# Sheet5.net
KiCad netlist of a schematic drawn in Altium Designer
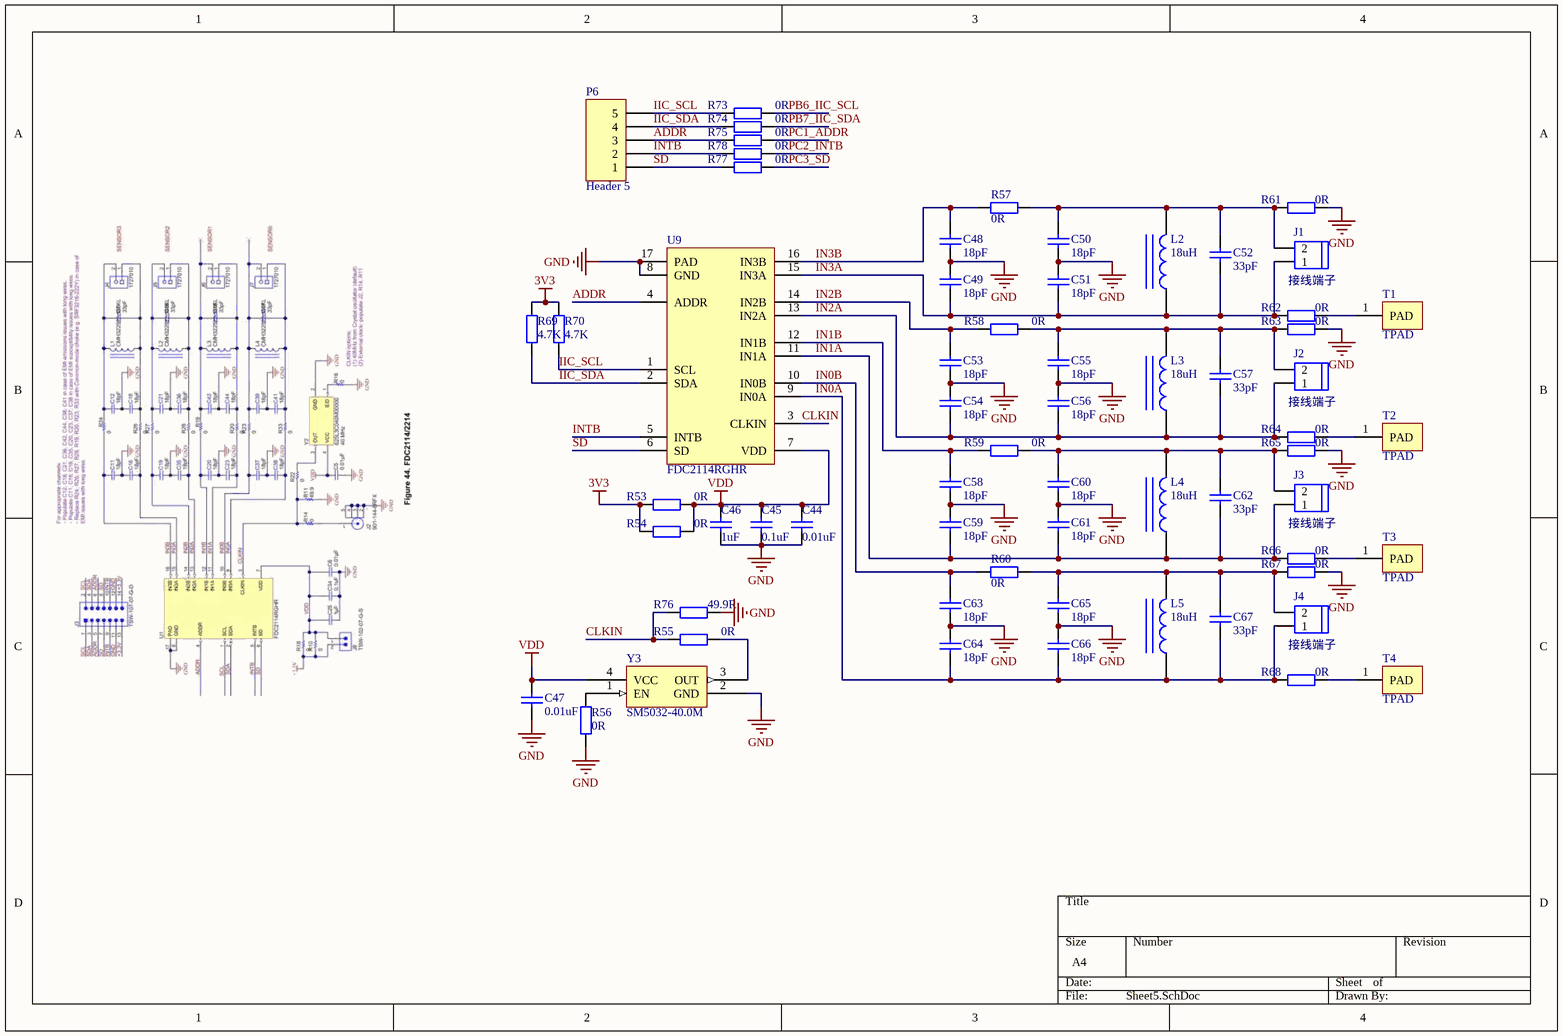
[diagram p0: Sheet5.SchDoc]

(export (version "E")
  (design (tool "Eeschema 10.0.6"))
  (components
    (comp (ref "C44")
      (value "0.01uF")
      (footprint "LC-0603_C")
      (description "贴片电容")
      (libsource (lib "Miscellaneous Devices LC") (part "0603 1uF (105) 10% 50V"))
    )
    (comp (ref "C45")
      (value "0.1uF")
      (footprint "LC-0603_C")
      (description "贴片电容")
      (libsource (lib "Miscellaneous Devices LC") (part "0603 1uF (105) 10% 50V"))
    )
    (comp (ref "C46")
      (value "1uF")
      (footprint "LC-0603_C")
      (description "贴片电容")
      (libsource (lib "Miscellaneous Devices LC") (part "0603 1uF (105) 10% 50V"))
    )
    (comp (ref "C47")
      (value "0.01uF")
      (footprint "LC-0603_C")
      (description "贴片电容")
      (libsource (lib "Miscellaneous Devices LC") (part "0603 1uF (105) 10% 50V"))
    )
    (comp (ref "C48")
      (value "18pF")
      (footprint "LC-0603_C")
      (description "贴片电容")
      (libsource (lib "Miscellaneous Devices LC") (part "0603 1uF (105) 10% 50V"))
    )
    (comp (ref "C49")
      (value "18pF")
      (footprint "LC-0603_C")
      (description "贴片电容")
      (libsource (lib "Miscellaneous Devices LC") (part "0603 1uF (105) 10% 50V"))
    )
    (comp (ref "C50")
      (value "18pF")
      (footprint "LC-0603_C")
      (description "贴片电容")
      (libsource (lib "Miscellaneous Devices LC") (part "0603 1uF (105) 10% 50V"))
    )
    (comp (ref "C51")
      (value "18pF")
      (footprint "LC-0603_C")
      (description "贴片电容")
      (libsource (lib "Miscellaneous Devices LC") (part "0603 1uF (105) 10% 50V"))
    )
    (comp (ref "C52")
      (value "33pF")
      (footprint "LC-0603_C")
      (description "贴片电容")
      (libsource (lib "Miscellaneous Devices LC") (part "0603 1uF (105) 10% 50V"))
    )
    (comp (ref "C53")
      (value "18pF")
      (footprint "LC-0603_C")
      (description "贴片电容")
      (libsource (lib "Miscellaneous Devices LC") (part "0603 1uF (105) 10% 50V"))
    )
    (comp (ref "C54")
      (value "18pF")
      (footprint "LC-0603_C")
      (description "贴片电容")
      (libsource (lib "Miscellaneous Devices LC") (part "0603 1uF (105) 10% 50V"))
    )
    (comp (ref "C55")
      (value "18pF")
      (footprint "LC-0603_C")
      (description "贴片电容")
      (libsource (lib "Miscellaneous Devices LC") (part "0603 1uF (105) 10% 50V"))
    )
    (comp (ref "C56")
      (value "18pF")
      (footprint "LC-0603_C")
      (description "贴片电容")
      (libsource (lib "Miscellaneous Devices LC") (part "0603 1uF (105) 10% 50V"))
    )
    (comp (ref "C57")
      (value "33pF")
      (footprint "LC-0603_C")
      (description "贴片电容")
      (libsource (lib "Miscellaneous Devices LC") (part "0603 1uF (105) 10% 50V"))
    )
    (comp (ref "C58")
      (value "18pF")
      (footprint "LC-0603_C")
      (description "贴片电容")
      (libsource (lib "Miscellaneous Devices LC") (part "0603 1uF (105) 10% 50V"))
    )
    (comp (ref "C59")
      (value "18pF")
      (footprint "LC-0603_C")
      (description "贴片电容")
      (libsource (lib "Miscellaneous Devices LC") (part "0603 1uF (105) 10% 50V"))
    )
    (comp (ref "C60")
      (value "18pF")
      (footprint "LC-0603_C")
      (description "贴片电容")
      (libsource (lib "Miscellaneous Devices LC") (part "0603 1uF (105) 10% 50V"))
    )
    (comp (ref "C61")
      (value "18pF")
      (footprint "LC-0603_C")
      (description "贴片电容")
      (libsource (lib "Miscellaneous Devices LC") (part "0603 1uF (105) 10% 50V"))
    )
    (comp (ref "C62")
      (value "33pF")
      (footprint "LC-0603_C")
      (description "贴片电容")
      (libsource (lib "Miscellaneous Devices LC") (part "0603 1uF (105) 10% 50V"))
    )
    (comp (ref "C63")
      (value "18pF")
      (footprint "LC-0603_C")
      (description "贴片电容")
      (libsource (lib "Miscellaneous Devices LC") (part "0603 1uF (105) 10% 50V"))
    )
    (comp (ref "C64")
      (value "18pF")
      (footprint "LC-0603_C")
      (description "贴片电容")
      (libsource (lib "Miscellaneous Devices LC") (part "0603 1uF (105) 10% 50V"))
    )
    (comp (ref "C65")
      (value "18pF")
      (footprint "LC-0603_C")
      (description "贴片电容")
      (libsource (lib "Miscellaneous Devices LC") (part "0603 1uF (105) 10% 50V"))
    )
    (comp (ref "C66")
      (value "18pF")
      (footprint "LC-0603_C")
      (description "贴片电容")
      (libsource (lib "Miscellaneous Devices LC") (part "0603 1uF (105) 10% 50V"))
    )
    (comp (ref "C67")
      (value "33pF")
      (footprint "LC-0603_C")
      (description "贴片电容")
      (libsource (lib "Miscellaneous Devices LC") (part "0603 1uF (105) 10% 50V"))
    )
    (comp (ref "J1")
      (value "接线端子")
      (footprint "CON_2_5.08B")
      (libsource (lib "Explorer STM32F407封装库") (part "HEAD2"))
    )
    (comp (ref "J2")
      (value "接线端子")
      (footprint "CON_2_5.08B")
      (libsource (lib "Explorer STM32F407封装库") (part "HEAD2"))
    )
    (comp (ref "J3")
      (value "接线端子")
      (footprint "CON_2_5.08B")
      (libsource (lib "Explorer STM32F407封装库") (part "HEAD2"))
    )
    (comp (ref "J4")
      (value "接线端子")
      (footprint "CON_2_5.08B")
      (libsource (lib "Explorer STM32F407封装库") (part "HEAD2"))
    )
    (comp (ref "L2")
      (value "18uH")
      (footprint "LC-0805_L")
      (description "贴片电感")
      (libsource (lib "Miscellaneous Devices LC") (part "0805 47uH 10%"))
    )
    (comp (ref "L3")
      (value "18uH")
      (footprint "LC-0805_L")
      (description "贴片电感")
      (libsource (lib "Miscellaneous Devices LC") (part "0805 47uH 10%"))
    )
    (comp (ref "L4")
      (value "18uH")
      (footprint "LC-0805_L")
      (description "贴片电感")
      (libsource (lib "Miscellaneous Devices LC") (part "0805 47uH 10%"))
    )
    (comp (ref "L5")
      (value "18uH")
      (footprint "LC-0805_L")
      (description "贴片电感")
      (libsource (lib "Miscellaneous Devices LC") (part "0805 47uH 10%"))
    )
    (comp (ref "P6")
      (value "Header 5")
      (footprint "HDR1X5")
      (description "Header, 5-Pin")
      (fields (field (name "PUBLISHER") "Altium Limited"))
      (libsource (lib "Sparks") (part "Header 5"))
    )
    (comp (ref "R53")
      (value "0R")
      (footprint "LC-0603_R")
      (description "贴片电阻")
      (libsource (lib "Miscellaneous Devices LC") (part "0603 1.5KΩ (1501) 1%"))
    )
    (comp (ref "R54")
      (value "0R")
      (footprint "LC-0603_R")
      (description "贴片电阻")
      (libsource (lib "Miscellaneous Devices LC") (part "0603 1.5KΩ (1501) 1%"))
    )
    (comp (ref "R55")
      (value "0R")
      (footprint "LC-0603_R")
      (description "贴片电阻")
      (libsource (lib "Miscellaneous Devices LC") (part "0603 1.5KΩ (1501) 1%"))
    )
    (comp (ref "R56")
      (value "0R")
      (footprint "LC-0603_R")
      (description "贴片电阻")
      (libsource (lib "") (part "0603 1.5KΩ (1501) 1%_1"))
    )
    (comp (ref "R57")
      (value "0R")
      (footprint "LC-0603_R")
      (description "贴片电阻")
      (libsource (lib "Miscellaneous Devices LC") (part "0603 1.5KΩ (1501) 1%"))
    )
    (comp (ref "R58")
      (value "0R")
      (footprint "LC-0603_R")
      (description "贴片电阻")
      (libsource (lib "Miscellaneous Devices LC") (part "0603 1.5KΩ (1501) 1%"))
    )
    (comp (ref "R59")
      (value "0R")
      (footprint "LC-0603_R")
      (description "贴片电阻")
      (libsource (lib "Miscellaneous Devices LC") (part "0603 1.5KΩ (1501) 1%"))
    )
    (comp (ref "R60")
      (value "0R")
      (footprint "LC-0603_R")
      (description "贴片电阻")
      (libsource (lib "Miscellaneous Devices LC") (part "0603 1.5KΩ (1501) 1%"))
    )
    (comp (ref "R61")
      (value "0R")
      (footprint "LC-0603_R")
      (description "贴片电阻")
      (libsource (lib "Miscellaneous Devices LC") (part "0603 1.5KΩ (1501) 1%"))
    )
    (comp (ref "R62")
      (value "0R")
      (footprint "LC-0603_R")
      (description "贴片电阻")
      (libsource (lib "Miscellaneous Devices LC") (part "0603 1.5KΩ (1501) 1%"))
    )
    (comp (ref "R63")
      (value "0R")
      (footprint "LC-0603_R")
      (description "贴片电阻")
      (libsource (lib "Miscellaneous Devices LC") (part "0603 1.5KΩ (1501) 1%"))
    )
    (comp (ref "R64")
      (value "0R")
      (footprint "LC-0603_R")
      (description "贴片电阻")
      (libsource (lib "Miscellaneous Devices LC") (part "0603 1.5KΩ (1501) 1%"))
    )
    (comp (ref "R65")
      (value "0R")
      (footprint "LC-0603_R")
      (description "贴片电阻")
      (libsource (lib "Miscellaneous Devices LC") (part "0603 1.5KΩ (1501) 1%"))
    )
    (comp (ref "R66")
      (value "0R")
      (footprint "LC-0603_R")
      (description "贴片电阻")
      (libsource (lib "Miscellaneous Devices LC") (part "0603 1.5KΩ (1501) 1%"))
    )
    (comp (ref "R67")
      (value "0R")
      (footprint "LC-0603_R")
      (description "贴片电阻")
      (libsource (lib "Miscellaneous Devices LC") (part "0603 1.5KΩ (1501) 1%"))
    )
    (comp (ref "R68")
      (value "0R")
      (footprint "LC-0603_R")
      (description "贴片电阻")
      (libsource (lib "Miscellaneous Devices LC") (part "0603 1.5KΩ (1501) 1%"))
    )
    (comp (ref "R69")
      (value "4.7K")
      (footprint "LC-0603_R")
      (description "贴片电阻")
      (libsource (lib "") (part "0603 1.5KΩ (1501) 1%_1"))
    )
    (comp (ref "R70")
      (value "4.7K")
      (footprint "LC-0603_R")
      (description "贴片电阻")
      (libsource (lib "") (part "0603 1.5KΩ (1501) 1%_1"))
    )
    (comp (ref "R73")
      (value "0R")
      (footprint "LC-0603_R")
      (description "贴片电阻")
      (libsource (lib "Miscellaneous Devices LC") (part "0603 1.5KΩ (1501) 1%"))
    )
    (comp (ref "R74")
      (value "0R")
      (footprint "LC-0603_R")
      (description "贴片电阻")
      (libsource (lib "Miscellaneous Devices LC") (part "0603 1.5KΩ (1501) 1%"))
    )
    (comp (ref "R75")
      (value "0R")
      (footprint "LC-0603_R")
      (description "贴片电阻")
      (libsource (lib "Miscellaneous Devices LC") (part "0603 1.5KΩ (1501) 1%"))
    )
    (comp (ref "R76")
      (value "49.9R")
      (footprint "LC-0603_R")
      (description "贴片电阻")
      (libsource (lib "Miscellaneous Devices LC") (part "0603 1.5KΩ (1501) 1%"))
    )
    (comp (ref "R77")
      (value "0R")
      (footprint "LC-0603_R")
      (description "贴片电阻")
      (libsource (lib "Miscellaneous Devices LC") (part "0603 1.5KΩ (1501) 1%"))
    )
    (comp (ref "R78")
      (value "0R")
      (footprint "LC-0603_R")
      (description "贴片电阻")
      (libsource (lib "Miscellaneous Devices LC") (part "0603 1.5KΩ (1501) 1%"))
    )
    (comp (ref "T1")
      (value "TPAD")
      (footprint "TOUCH")
      (description "触摸按键")
      (libsource (lib "CD's_LIB_2018") (part "TPAD"))
    )
    (comp (ref "T2")
      (value "TPAD")
      (footprint "TOUCH")
      (description "触摸按键")
      (libsource (lib "CD's_LIB_2018") (part "TPAD"))
    )
    (comp (ref "T3")
      (value "TPAD")
      (footprint "TOUCH")
      (description "触摸按键")
      (libsource (lib "CD's_LIB_2018") (part "TPAD"))
    )
    (comp (ref "T4")
      (value "TPAD")
      (footprint "TOUCH")
      (description "触摸按键")
      (libsource (lib "CD's_LIB_2018") (part "TPAD"))
    )
    (comp (ref "U9")
      (value "FDC2114RGHR")
      (footprint "QFN16-05")
      (description "电容检测传感器")
      (libsource (lib "liu_2016") (part "FDC2114RGHR"))
    )
    (comp (ref "Y3")
      (value "SM5032-40.0M")
      (footprint "CD's_LIB_2018:XTAL_5032")
      (description "有源晶振")
      (libsource (lib "CD's_LIB_2018") (part "SM5032"))
    )
  )
  (nets
    (net (code "1") (name "/ADDR") (class "Default")
      (node (ref "P6") (pin "3") (pinfunction "3_3") (pintype "passive"))
      (node (ref "R75") (pin "1") (pinfunction "1_1") (pintype "passive"))
      (node (ref "U9") (pin "4") (pinfunction "ADDR_4") (pintype "passive"))
    )
    (net (code "2") (name "/CLKIN") (class "Default")
      (node (ref "R55") (pin "1") (pinfunction "1_1") (pintype "passive"))
      (node (ref "R76") (pin "1") (pinfunction "1_1") (pintype "passive"))
      (node (ref "U9") (pin "3") (pinfunction "CLKIN_3") (pintype "passive"))
    )
    (net (code "3") (name "/IIC_SCL") (class "Default")
      (node (ref "P6") (pin "5") (pinfunction "5_5") (pintype "passive"))
      (node (ref "R70") (pin "1") (pinfunction "1_1") (pintype "passive"))
      (node (ref "R73") (pin "1") (pinfunction "1_1") (pintype "passive"))
      (node (ref "U9") (pin "1") (pinfunction "SCL_1") (pintype "passive"))
    )
    (net (code "4") (name "/IIC_SDA") (class "Default")
      (node (ref "P6") (pin "4") (pinfunction "4_4") (pintype "passive"))
      (node (ref "R69") (pin "1") (pinfunction "1_1") (pintype "passive"))
      (node (ref "R74") (pin "1") (pinfunction "1_1") (pintype "passive"))
      (node (ref "U9") (pin "2") (pinfunction "SDA_2") (pintype "passive"))
    )
    (net (code "5") (name "/IN0A") (class "Default")
      (node (ref "C64") (pin "1") (pinfunction "1_1") (pintype "passive"))
      (node (ref "C66") (pin "1") (pinfunction "1_1") (pintype "passive"))
      (node (ref "C67") (pin "1") (pinfunction "1_1") (pintype "passive"))
      (node (ref "J4") (pin "1") (pinfunction "1_1") (pintype "passive"))
      (node (ref "L5") (pin "1") (pinfunction "1_1") (pintype "passive"))
      (node (ref "R68") (pin "1") (pinfunction "1_1") (pintype "passive"))
      (node (ref "U9") (pin "9") (pinfunction "IN0A_9") (pintype "passive"))
    )
    (net (code "6") (name "/IN0B") (class "Default")
      (node (ref "C63") (pin "2") (pinfunction "2_2") (pintype "passive"))
      (node (ref "R60") (pin "1") (pinfunction "1_1") (pintype "passive"))
      (node (ref "U9") (pin "10") (pinfunction "IN0B_10") (pintype "passive"))
    )
    (net (code "7") (name "/IN1A") (class "Default")
      (node (ref "C59") (pin "1") (pinfunction "1_1") (pintype "passive"))
      (node (ref "C61") (pin "1") (pinfunction "1_1") (pintype "passive"))
      (node (ref "C62") (pin "1") (pinfunction "1_1") (pintype "passive"))
      (node (ref "J3") (pin "1") (pinfunction "1_1") (pintype "passive"))
      (node (ref "L4") (pin "1") (pinfunction "1_1") (pintype "passive"))
      (node (ref "R66") (pin "1") (pinfunction "1_1") (pintype "passive"))
      (node (ref "U9") (pin "11") (pinfunction "IN1A_11") (pintype "passive"))
    )
    (net (code "8") (name "/IN1B") (class "Default")
      (node (ref "C58") (pin "2") (pinfunction "2_2") (pintype "passive"))
      (node (ref "R59") (pin "1") (pinfunction "1_1") (pintype "passive"))
      (node (ref "U9") (pin "12") (pinfunction "IN1B_12") (pintype "passive"))
    )
    (net (code "9") (name "/IN2A") (class "Default")
      (node (ref "C54") (pin "1") (pinfunction "1_1") (pintype "passive"))
      (node (ref "C56") (pin "1") (pinfunction "1_1") (pintype "passive"))
      (node (ref "C57") (pin "1") (pinfunction "1_1") (pintype "passive"))
      (node (ref "J2") (pin "1") (pinfunction "1_1") (pintype "passive"))
      (node (ref "L3") (pin "1") (pinfunction "1_1") (pintype "passive"))
      (node (ref "R64") (pin "1") (pinfunction "1_1") (pintype "passive"))
      (node (ref "U9") (pin "13") (pinfunction "IN2A_13") (pintype "passive"))
    )
    (net (code "10") (name "/IN2B") (class "Default")
      (node (ref "C53") (pin "2") (pinfunction "2_2") (pintype "passive"))
      (node (ref "R58") (pin "1") (pinfunction "1_1") (pintype "passive"))
      (node (ref "U9") (pin "14") (pinfunction "IN2B_14") (pintype "passive"))
    )
    (net (code "11") (name "/IN3A") (class "Default")
      (node (ref "C49") (pin "1") (pinfunction "1_1") (pintype "passive"))
      (node (ref "C51") (pin "1") (pinfunction "1_1") (pintype "passive"))
      (node (ref "C52") (pin "1") (pinfunction "1_1") (pintype "passive"))
      (node (ref "J1") (pin "1") (pinfunction "1_1") (pintype "passive"))
      (node (ref "L2") (pin "1") (pinfunction "1_1") (pintype "passive"))
      (node (ref "R62") (pin "1") (pinfunction "1_1") (pintype "passive"))
      (node (ref "U9") (pin "15") (pinfunction "IN3A_15") (pintype "passive"))
    )
    (net (code "12") (name "/IN3B") (class "Default")
      (node (ref "C48") (pin "2") (pinfunction "2_2") (pintype "passive"))
      (node (ref "R57") (pin "1") (pinfunction "1_1") (pintype "passive"))
      (node (ref "U9") (pin "16") (pinfunction "IN3B_16") (pintype "passive"))
    )
    (net (code "13") (name "/INTB") (class "Default")
      (node (ref "P6") (pin "2") (pinfunction "2_2") (pintype "passive"))
      (node (ref "R78") (pin "1") (pinfunction "1_1") (pintype "passive"))
      (node (ref "U9") (pin "5") (pinfunction "INTB_5") (pintype "passive"))
    )
    (net (code "14") (name "/PB6_IIC_SCL") (class "Default")
      (node (ref "R73") (pin "2") (pinfunction "2_2") (pintype "passive"))
    )
    (net (code "15") (name "/PB7_IIC_SDA") (class "Default")
      (node (ref "R74") (pin "2") (pinfunction "2_2") (pintype "passive"))
    )
    (net (code "16") (name "/PC1_ADDR") (class "Default")
      (node (ref "R75") (pin "2") (pinfunction "2_2") (pintype "passive"))
    )
    (net (code "17") (name "/PC2_INTB") (class "Default")
      (node (ref "R78") (pin "2") (pinfunction "2_2") (pintype "passive"))
    )
    (net (code "18") (name "/PC3_SD") (class "Default")
      (node (ref "R77") (pin "2") (pinfunction "2_2") (pintype "passive"))
    )
    (net (code "19") (name "/SD") (class "Default")
      (node (ref "P6") (pin "1") (pinfunction "1_1") (pintype "passive"))
      (node (ref "R77") (pin "1") (pinfunction "1_1") (pintype "passive"))
      (node (ref "U9") (pin "6") (pinfunction "SD_6") (pintype "passive"))
    )
    (net (code "20") (name "3V3") (class "Default")
      (node (ref "R53") (pin "1") (pinfunction "1_1") (pintype "passive"))
      (node (ref "R54") (pin "1") (pinfunction "1_1") (pintype "passive"))
      (node (ref "R69") (pin "2") (pinfunction "2_2") (pintype "passive"))
      (node (ref "R70") (pin "2") (pinfunction "2_2") (pintype "passive"))
    )
    (net (code "21") (name "GND") (class "Default")
      (node (ref "C44") (pin "1") (pinfunction "1_1") (pintype "passive"))
      (node (ref "C45") (pin "1") (pinfunction "1_1") (pintype "passive"))
      (node (ref "C46") (pin "1") (pinfunction "1_1") (pintype "passive"))
      (node (ref "C47") (pin "1") (pinfunction "1_1") (pintype "passive"))
      (node (ref "C48") (pin "1") (pinfunction "1_1") (pintype "passive"))
      (node (ref "C49") (pin "2") (pinfunction "2_2") (pintype "passive"))
      (node (ref "C50") (pin "1") (pinfunction "1_1") (pintype "passive"))
      (node (ref "C51") (pin "2") (pinfunction "2_2") (pintype "passive"))
      (node (ref "C53") (pin "1") (pinfunction "1_1") (pintype "passive"))
      (node (ref "C54") (pin "2") (pinfunction "2_2") (pintype "passive"))
      (node (ref "C55") (pin "1") (pinfunction "1_1") (pintype "passive"))
      (node (ref "C56") (pin "2") (pinfunction "2_2") (pintype "passive"))
      (node (ref "C58") (pin "1") (pinfunction "1_1") (pintype "passive"))
      (node (ref "C59") (pin "2") (pinfunction "2_2") (pintype "passive"))
      (node (ref "C60") (pin "1") (pinfunction "1_1") (pintype "passive"))
      (node (ref "C61") (pin "2") (pinfunction "2_2") (pintype "passive"))
      (node (ref "C63") (pin "1") (pinfunction "1_1") (pintype "passive"))
      (node (ref "C64") (pin "2") (pinfunction "2_2") (pintype "passive"))
      (node (ref "C65") (pin "1") (pinfunction "1_1") (pintype "passive"))
      (node (ref "C66") (pin "2") (pinfunction "2_2") (pintype "passive"))
      (node (ref "R56") (pin "1") (pinfunction "1_1") (pintype "passive"))
      (node (ref "R61") (pin "2") (pinfunction "2_2") (pintype "passive"))
      (node (ref "R63") (pin "2") (pinfunction "2_2") (pintype "passive"))
      (node (ref "R65") (pin "2") (pinfunction "2_2") (pintype "passive"))
      (node (ref "R67") (pin "2") (pinfunction "2_2") (pintype "passive"))
      (node (ref "R76") (pin "2") (pinfunction "2_2") (pintype "passive"))
      (node (ref "U9") (pin "17") (pinfunction "PAD_17") (pintype "passive"))
      (node (ref "U9") (pin "8") (pinfunction "GND_8") (pintype "passive"))
      (node (ref "Y3") (pin "2") (pinfunction "GND_2") (pintype "passive"))
    )
    (net (code "22") (name "Net-(C50-Pad2)") (class "Default")
      (node (ref "C50") (pin "2") (pinfunction "2_2") (pintype "passive"))
      (node (ref "C52") (pin "2") (pinfunction "2_2") (pintype "passive"))
      (node (ref "J1") (pin "2") (pinfunction "2_2") (pintype "passive"))
      (node (ref "L2") (pin "2") (pinfunction "2_2") (pintype "passive"))
      (node (ref "R57") (pin "2") (pinfunction "2_2") (pintype "passive"))
      (node (ref "R61") (pin "1") (pinfunction "1_1") (pintype "passive"))
    )
    (net (code "23") (name "Net-(C55-Pad2)") (class "Default")
      (node (ref "C55") (pin "2") (pinfunction "2_2") (pintype "passive"))
      (node (ref "C57") (pin "2") (pinfunction "2_2") (pintype "passive"))
      (node (ref "J2") (pin "2") (pinfunction "2_2") (pintype "passive"))
      (node (ref "L3") (pin "2") (pinfunction "2_2") (pintype "passive"))
      (node (ref "R58") (pin "2") (pinfunction "2_2") (pintype "passive"))
      (node (ref "R63") (pin "1") (pinfunction "1_1") (pintype "passive"))
    )
    (net (code "24") (name "Net-(C60-Pad2)") (class "Default")
      (node (ref "C60") (pin "2") (pinfunction "2_2") (pintype "passive"))
      (node (ref "C62") (pin "2") (pinfunction "2_2") (pintype "passive"))
      (node (ref "J3") (pin "2") (pinfunction "2_2") (pintype "passive"))
      (node (ref "L4") (pin "2") (pinfunction "2_2") (pintype "passive"))
      (node (ref "R59") (pin "2") (pinfunction "2_2") (pintype "passive"))
      (node (ref "R65") (pin "1") (pinfunction "1_1") (pintype "passive"))
    )
    (net (code "25") (name "Net-(C65-Pad2)") (class "Default")
      (node (ref "C65") (pin "2") (pinfunction "2_2") (pintype "passive"))
      (node (ref "C67") (pin "2") (pinfunction "2_2") (pintype "passive"))
      (node (ref "J4") (pin "2") (pinfunction "2_2") (pintype "passive"))
      (node (ref "L5") (pin "2") (pinfunction "2_2") (pintype "passive"))
      (node (ref "R60") (pin "2") (pinfunction "2_2") (pintype "passive"))
      (node (ref "R67") (pin "1") (pinfunction "1_1") (pintype "passive"))
    )
    (net (code "26") (name "Net-(T1-PAD)") (class "Default")
      (node (ref "R62") (pin "2") (pinfunction "2_2") (pintype "passive"))
      (node (ref "T1") (pin "1") (pinfunction "PAD_1") (pintype "passive"))
    )
    (net (code "27") (name "Net-(T2-PAD)") (class "Default")
      (node (ref "R64") (pin "2") (pinfunction "2_2") (pintype "passive"))
      (node (ref "T2") (pin "1") (pinfunction "PAD_1") (pintype "passive"))
    )
    (net (code "28") (name "Net-(T3-PAD)") (class "Default")
      (node (ref "R66") (pin "2") (pinfunction "2_2") (pintype "passive"))
      (node (ref "T3") (pin "1") (pinfunction "PAD_1") (pintype "passive"))
    )
    (net (code "29") (name "Net-(T4-PAD)") (class "Default")
      (node (ref "R68") (pin "2") (pinfunction "2_2") (pintype "passive"))
      (node (ref "T4") (pin "1") (pinfunction "PAD_1") (pintype "passive"))
    )
    (net (code "30") (name "Net-(Y3-EN)") (class "Default")
      (node (ref "R56") (pin "2") (pinfunction "2_2") (pintype "passive"))
      (node (ref "Y3") (pin "1") (pinfunction "EN_1") (pintype "input"))
    )
    (net (code "31") (name "Net-(Y3-OUT)") (class "Default")
      (node (ref "R55") (pin "2") (pinfunction "2_2") (pintype "passive"))
      (node (ref "Y3") (pin "3") (pinfunction "OUT_3") (pintype "output"))
    )
    (net (code "32") (name "VDD") (class "Default")
      (node (ref "C44") (pin "2") (pinfunction "2_2") (pintype "passive"))
      (node (ref "C45") (pin "2") (pinfunction "2_2") (pintype "passive"))
      (node (ref "C46") (pin "2") (pinfunction "2_2") (pintype "passive"))
      (node (ref "C47") (pin "2") (pinfunction "2_2") (pintype "passive"))
      (node (ref "R53") (pin "2") (pinfunction "2_2") (pintype "passive"))
      (node (ref "R54") (pin "2") (pinfunction "2_2") (pintype "passive"))
      (node (ref "U9") (pin "7") (pinfunction "VDD_7") (pintype "passive"))
      (node (ref "Y3") (pin "4") (pinfunction "VCC_4") (pintype "passive"))
    )
  )
)
